# 20160901_MMPLATES.net
KiCad netlist of a schematic drawn in EAGLE
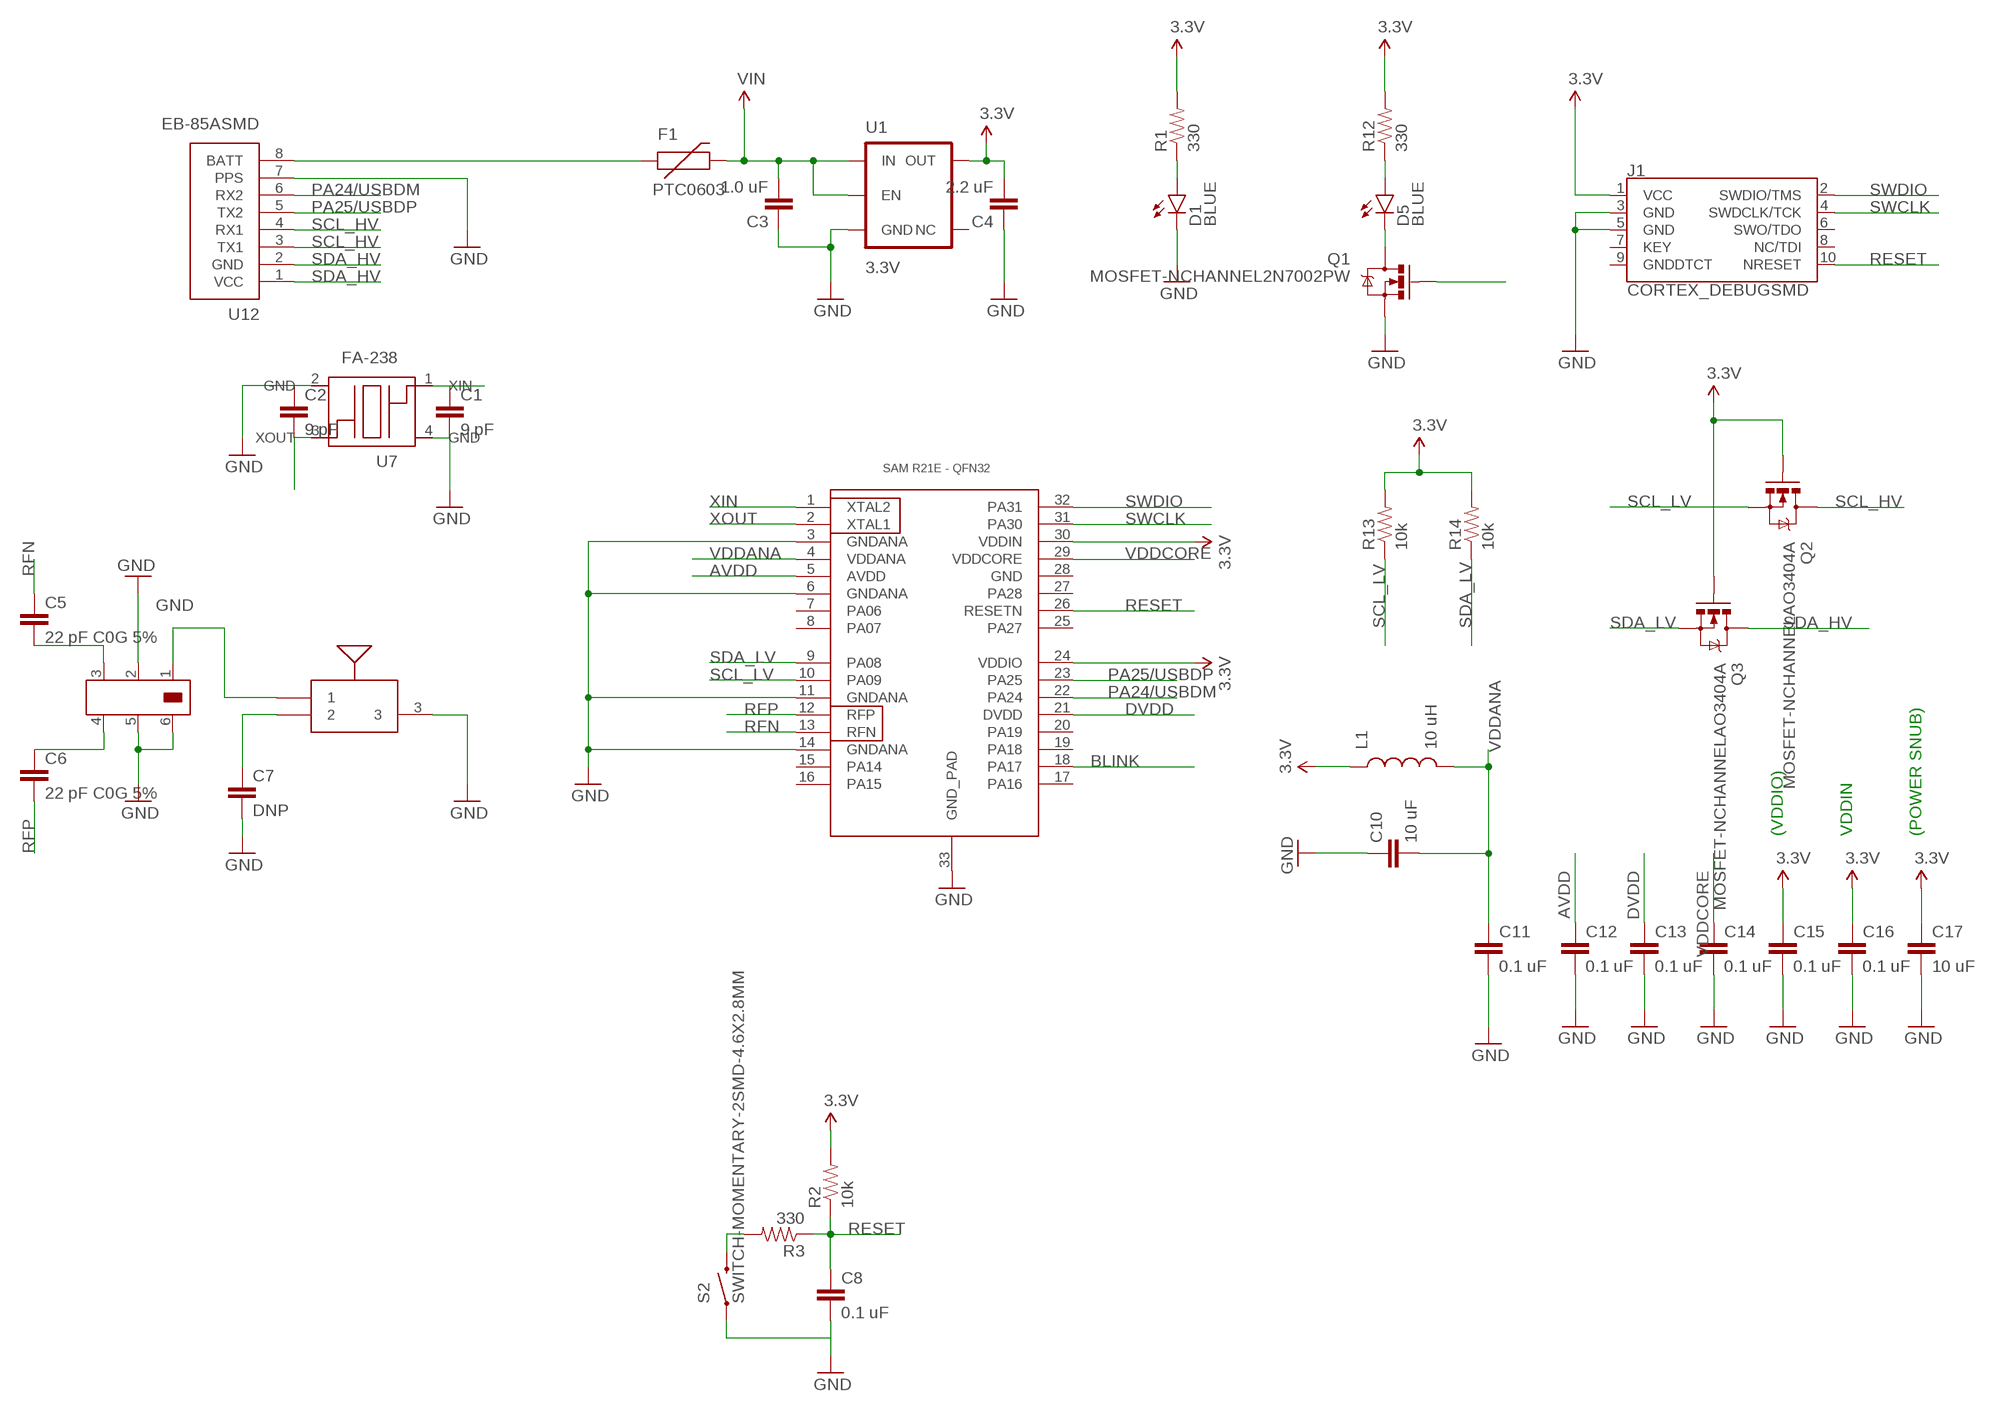
[diagram p0: schematic, sheet 1, part 1 of 2]
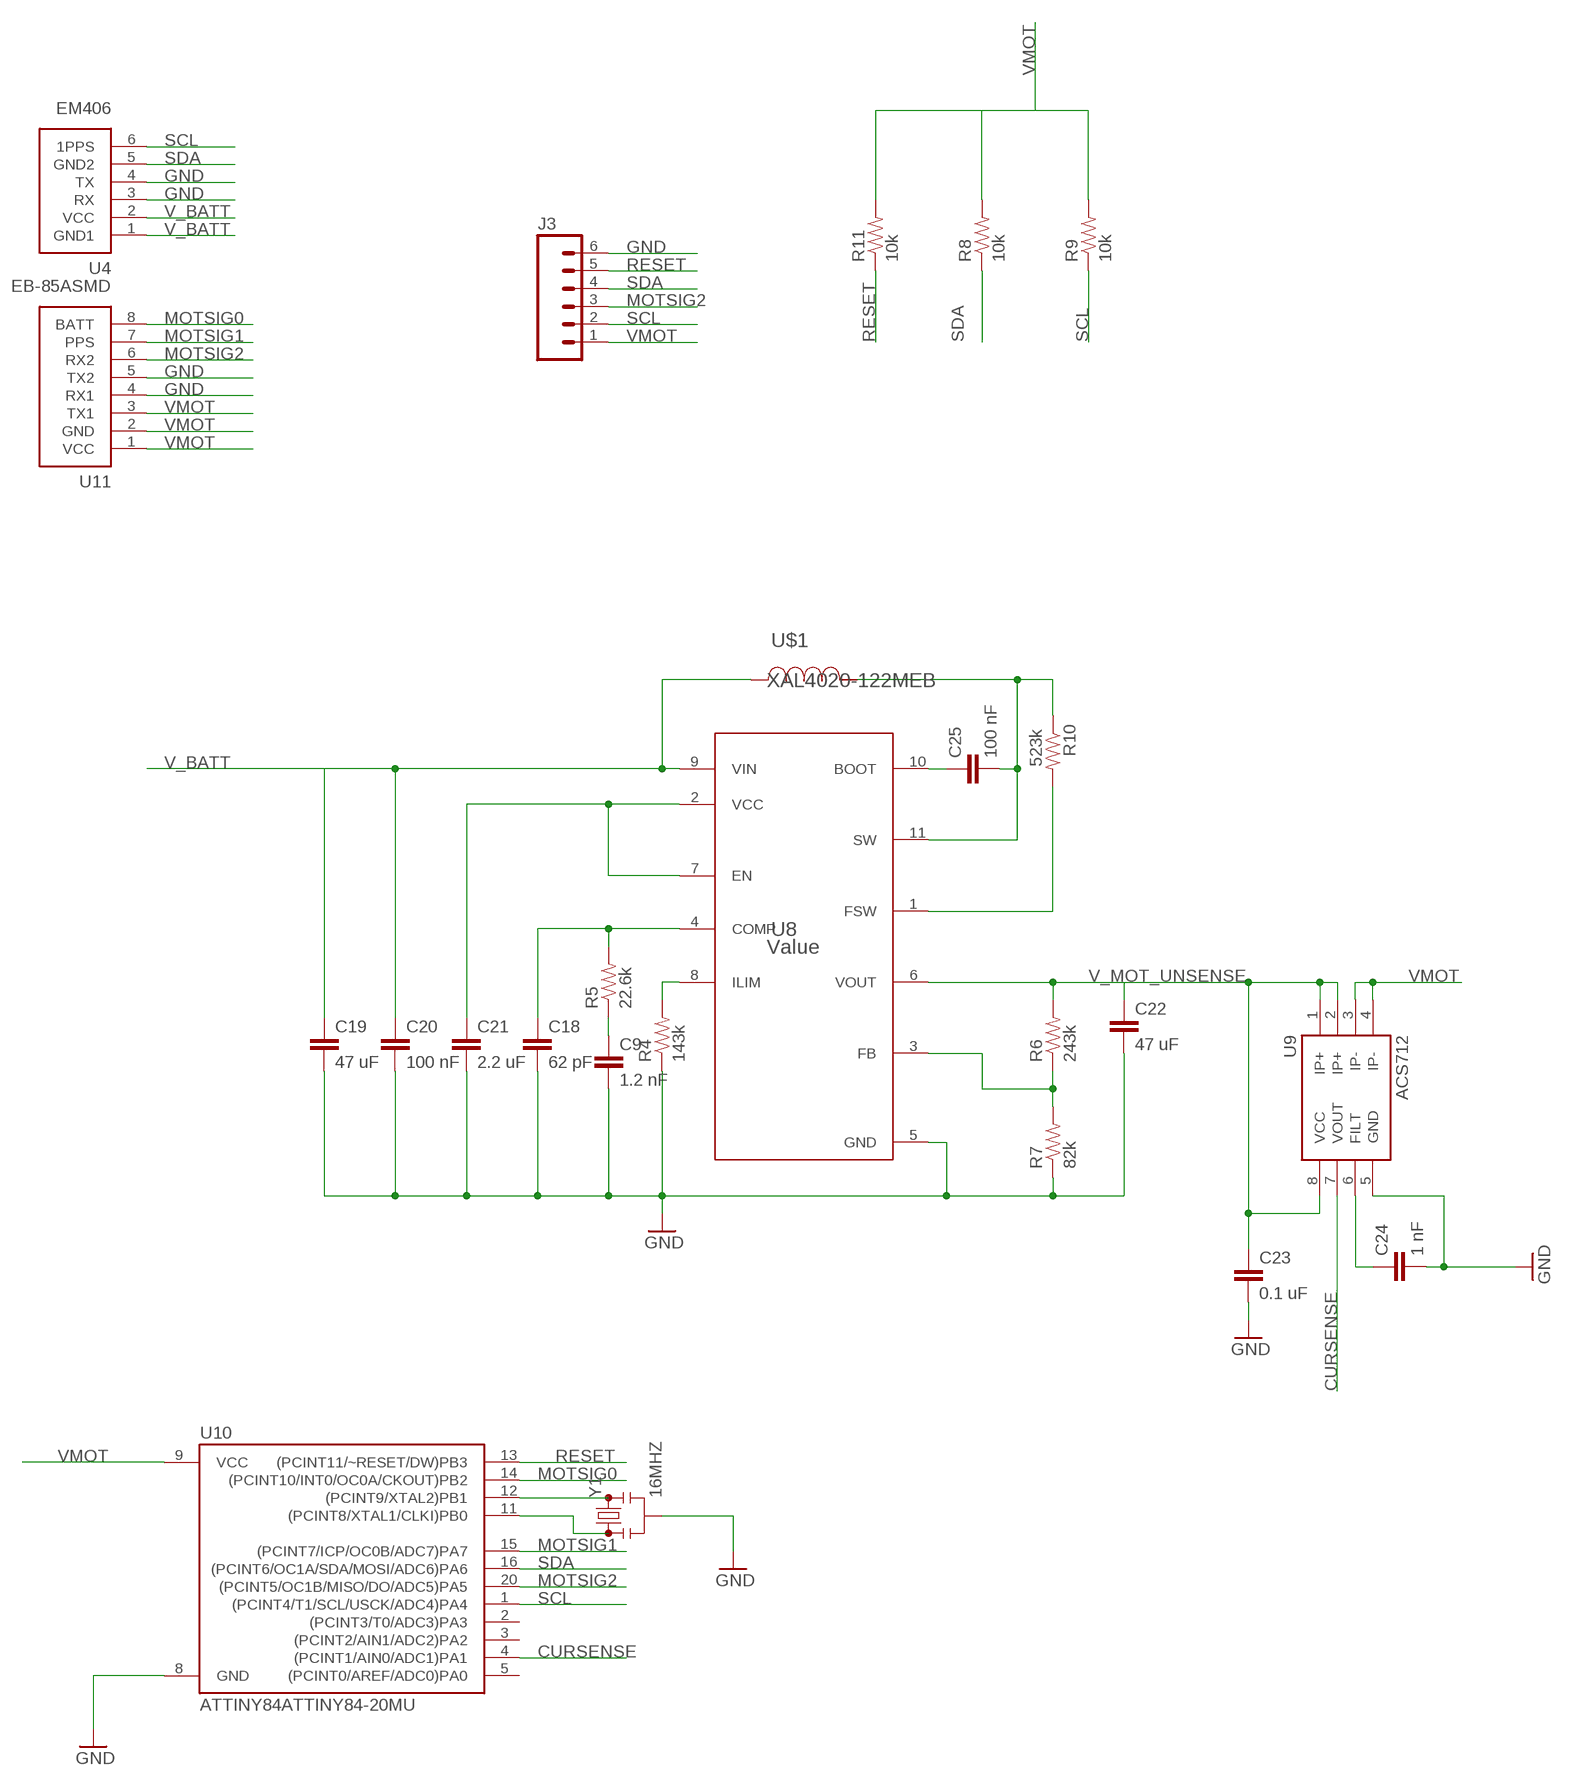
[diagram p1: schematic, sheet 1, part 2 of 2]

(export (version "E")
  (design (tool "Eeschema 10.0.6"))
  (components
    (comp (ref "C1")
      (value "9 pF")
      (footprint "eagle-import:0402-CAP")
      (libsource (lib "eagle-import") (part "CAP0402-CAP"))
    )
    (comp (ref "C2")
      (value "9 pF")
      (footprint "eagle-import:0402-CAP")
      (libsource (lib "eagle-import") (part "CAP0402-CAP"))
    )
    (comp (ref "C3")
      (value "1.0 uF")
      (footprint "eagle-import:0402-CAP")
      (libsource (lib "eagle-import") (part "CAP0402-CAP"))
    )
    (comp (ref "C4")
      (value "2.2 uF")
      (footprint "eagle-import:0402-CAP")
      (libsource (lib "eagle-import") (part "CAP0402-CAP"))
    )
    (comp (ref "C5")
      (value "22 pF C0G 5%")
      (footprint "eagle-import:0402-CAP")
      (libsource (lib "eagle-import") (part "CAP0402-CAP"))
    )
    (comp (ref "C6")
      (value "22 pF C0G 5%")
      (footprint "eagle-import:0402-CAP")
      (libsource (lib "eagle-import") (part "CAP0402-CAP"))
    )
    (comp (ref "C7")
      (value "DNP")
      (footprint "eagle-import:0402-CAP")
      (libsource (lib "eagle-import") (part "CAP0402-CAP"))
    )
    (comp (ref "C8")
      (value "0.1 uF")
      (footprint "eagle-import:0402-CAP")
      (libsource (lib "eagle-import") (part "CAP0402-CAP"))
    )
    (comp (ref "C9")
      (value "1.2 nF")
      (footprint "eagle-import:0805")
      (libsource (lib "eagle-import") (part "CAP0805"))
    )
    (comp (ref "C10")
      (value "10 uF")
      (footprint "eagle-import:0402-CAP")
      (libsource (lib "eagle-import") (part "CAP0402-CAP"))
    )
    (comp (ref "C11")
      (value "0.1 uF")
      (footprint "eagle-import:0402-CAP")
      (libsource (lib "eagle-import") (part "CAP0402-CAP"))
    )
    (comp (ref "C12")
      (value "0.1 uF")
      (footprint "eagle-import:0402-CAP")
      (libsource (lib "eagle-import") (part "CAP0402-CAP"))
    )
    (comp (ref "C13")
      (value "0.1 uF")
      (footprint "eagle-import:0402-CAP")
      (libsource (lib "eagle-import") (part "CAP0402-CAP"))
    )
    (comp (ref "C14")
      (value "0.1 uF")
      (footprint "eagle-import:0402-CAP")
      (libsource (lib "eagle-import") (part "CAP0402-CAP"))
    )
    (comp (ref "C15")
      (value "0.1 uF")
      (footprint "eagle-import:0402-CAP")
      (libsource (lib "eagle-import") (part "CAP0402-CAP"))
    )
    (comp (ref "C16")
      (value "0.1 uF")
      (footprint "eagle-import:0402-CAP")
      (libsource (lib "eagle-import") (part "CAP0402-CAP"))
    )
    (comp (ref "C17")
      (value "10 uF")
      (footprint "eagle-import:0402-CAP")
      (libsource (lib "eagle-import") (part "CAP0402-CAP"))
    )
    (comp (ref "C18")
      (value "62 pF")
      (footprint "eagle-import:0805")
      (libsource (lib "eagle-import") (part "CAP0805"))
    )
    (comp (ref "C19")
      (value "47 uF")
      (footprint "eagle-import:1206")
      (libsource (lib "eagle-import") (part "CAP1206"))
    )
    (comp (ref "C20")
      (value "100 nF")
      (footprint "eagle-import:0402-CAP")
      (libsource (lib "eagle-import") (part "CAP0402-CAP"))
    )
    (comp (ref "C21")
      (value "2.2 uF")
      (footprint "eagle-import:0603-CAP")
      (libsource (lib "eagle-import") (part "CAP0603-CAP"))
    )
    (comp (ref "C22")
      (value "47 uF")
      (footprint "eagle-import:1206")
      (libsource (lib "eagle-import") (part "CAP1206"))
    )
    (comp (ref "C23")
      (value "0.1 uF")
      (footprint "eagle-import:0402-CAP")
      (libsource (lib "eagle-import") (part "CAP0402-CAP"))
    )
    (comp (ref "C24")
      (value "1 nF")
      (footprint "eagle-import:0402-CAP")
      (libsource (lib "eagle-import") (part "CAP0402-CAP"))
    )
    (comp (ref "C25")
      (value "100 nF")
      (footprint "eagle-import:0402-CAP")
      (libsource (lib "eagle-import") (part "CAP0402-CAP"))
    )
    (comp (ref "D1")
      (value "BLUE")
      (footprint "eagle-import:LED-0603")
      (libsource (lib "eagle-import") (part "LED-BLUE0603"))
    )
    (comp (ref "D5")
      (value "BLUE")
      (footprint "eagle-import:LED-0603")
      (libsource (lib "eagle-import") (part "LED-BLUE0603"))
    )
    (comp (ref "F1")
      (value "PTC0603")
      (footprint "eagle-import:0603")
      (libsource (lib "eagle-import") (part "PTC0603"))
    )
    (comp (ref "J1")
      (value "CORTEX_DEBUGSMD")
      (footprint "eagle-import:SAMTECH_FTSH-105-01")
      (libsource (lib "eagle-import") (part "CORTEX_DEBUGSMD"))
    )
    (comp (ref "J3")
      (value "M06SMD-1MM")
      (footprint "eagle-import:1X06-1MM")
      (libsource (lib "eagle-import") (part "M06SMD-1MM"))
    )
    (comp (ref "L1")
      (value "10 uH")
      (footprint "eagle-import:0603")
      (libsource (lib "eagle-import") (part "INDUCTOR0603"))
    )
    (comp (ref "Q1")
      (value "MOSFET-NCHANNEL2N7002PW")
      (footprint "eagle-import:SOT323")
      (libsource (lib "eagle-import") (part "MOSFET-NCHANNEL2N7002PW"))
    )
    (comp (ref "Q2")
      (value "MOSFET-NCHANNELAO3404A")
      (footprint "eagle-import:SOT23-3")
      (libsource (lib "eagle-import") (part "MOSFET-NCHANNELAO3404A"))
    )
    (comp (ref "Q3")
      (value "MOSFET-NCHANNELAO3404A")
      (footprint "eagle-import:SOT23-3")
      (libsource (lib "eagle-import") (part "MOSFET-NCHANNELAO3404A"))
    )
    (comp (ref "R1")
      (value "330")
      (footprint "eagle-import:0402-RES")
      (libsource (lib "eagle-import") (part "RESISTOR0402-RES"))
    )
    (comp (ref "R2")
      (value "10k")
      (footprint "eagle-import:0402-RES")
      (libsource (lib "eagle-import") (part "RESISTOR0402-RES"))
    )
    (comp (ref "R3")
      (value "330")
      (footprint "eagle-import:0402-RES")
      (libsource (lib "eagle-import") (part "RESISTOR0402-RES"))
    )
    (comp (ref "R4")
      (value "143k")
      (footprint "eagle-import:1206")
      (libsource (lib "eagle-import") (part "SparkFun-Resistors_RESISTOR1206"))
    )
    (comp (ref "R5")
      (value "22.6k")
      (footprint "eagle-import:0402-RES")
      (libsource (lib "eagle-import") (part "RESISTOR0402-RES"))
    )
    (comp (ref "R6")
      (value "243k")
      (footprint "eagle-import:0402-RES")
      (libsource (lib "eagle-import") (part "RESISTOR0402-RES"))
    )
    (comp (ref "R7")
      (value "82k")
      (footprint "eagle-import:0603-RES")
      (libsource (lib "eagle-import") (part "RESISTOR0603-RES"))
    )
    (comp (ref "R8")
      (value "10k")
      (footprint "eagle-import:0402-RES")
      (libsource (lib "eagle-import") (part "RESISTOR0402-RES"))
    )
    (comp (ref "R9")
      (value "10k")
      (footprint "eagle-import:0402-RES")
      (libsource (lib "eagle-import") (part "RESISTOR0402-RES"))
    )
    (comp (ref "R10")
      (value "523k")
      (footprint "eagle-import:1206")
      (libsource (lib "eagle-import") (part "SparkFun-Resistors_RESISTOR1206"))
    )
    (comp (ref "R11")
      (value "10k")
      (footprint "eagle-import:0402-RES")
      (libsource (lib "eagle-import") (part "RESISTOR0402-RES"))
    )
    (comp (ref "R12")
      (value "330")
      (footprint "eagle-import:0402-RES")
      (libsource (lib "eagle-import") (part "RESISTOR0402-RES"))
    )
    (comp (ref "R13")
      (value "10k")
      (footprint "eagle-import:0402-RES")
      (libsource (lib "eagle-import") (part "RESISTOR0402-RES"))
    )
    (comp (ref "R14")
      (value "10k")
      (footprint "eagle-import:0402-RES")
      (libsource (lib "eagle-import") (part "RESISTOR0402-RES"))
    )
    (comp (ref "S2")
      (value "SWITCH-MOMENTARY-2SMD-4.6X2.8MM")
      (footprint "eagle-import:TACTILE_SWITCH_SMD_4.6X2.8MM")
      (libsource (lib "eagle-import") (part "SWITCH-MOMENTARY-2SMD-4.6X2.8MM"))
    )
    (comp (ref "U$1")
      (value "XAL4020-122MEB")
      (footprint "eagle-import:XAL4020")
      (libsource (lib "eagle-import") (part "XAL4020-122MEB"))
    )
    (comp (ref "U1")
      (value "3.3V")
      (footprint "eagle-import:SOT23-5")
      (libsource (lib "eagle-import") (part "V_REG_AP2112K-3.3V"))
    )
    (comp (ref "U2")
      (value "ATSAMR21E18A-MUT")
      (footprint "eagle-import:QFN32")
      (libsource (lib "eagle-import") (part "ATSAMR21E18A-MUT"))
    )
    (comp (ref "U4")
      (value "EM406")
      (footprint "eagle-import:EM406")
      (libsource (lib "eagle-import") (part "EM406"))
    )
    (comp (ref "U5")
      (value "PULSE_ANT_2.4GHZ")
      (footprint "eagle-import:ANT_BAR")
      (libsource (lib "eagle-import") (part "PULSE_ANT_2.4GHZ"))
    )
    (comp (ref "U6")
      (value "JOHANSON_2450BM15A0015E")
      (footprint "eagle-import:0805_BALUN")
      (libsource (lib "eagle-import") (part "JOHANSON_2450BM15A0015E"))
    )
    (comp (ref "U7")
      (value "FA-238")
      (footprint "eagle-import:FA-238")
      (libsource (lib "eagle-import") (part "FA-238"))
    )
    (comp (ref "U8")
      (value "Value")
      (footprint "eagle-import:RNR0011A")
      (fields
        (field (name "MANUFACTURER") "Texas Instruments")
        (field (name "MANUFACTURER_PART_NUMBER") "TPS61089RNRR")
      )
      (libsource (lib "eagle-import") (part "TPS61089RNRR"))
    )
    (comp (ref "U9")
      (value "ACS712")
      (footprint "eagle-import:SO08")
      (libsource (lib "eagle-import") (part "ACS712"))
    )
    (comp (ref "U10")
      (value "ATTINY84ATTINY84-20MU")
      (footprint "eagle-import:QFN20")
      (libsource (lib "eagle-import") (part "ATTINY84ATTINY84-20MU"))
    )
    (comp (ref "U11")
      (value "EB-85ASMD")
      (footprint "eagle-import:EB-85A")
      (libsource (lib "eagle-import") (part "EB-85ASMD"))
    )
    (comp (ref "U12")
      (value "EB-85ASMD")
      (footprint "eagle-import:EB-85A")
      (libsource (lib "eagle-import") (part "EB-85ASMD"))
    )
    (comp (ref "Y1")
      (value "16MHZ")
      (footprint "eagle-import:RESONATOR-SMD")
      (libsource (lib "eagle-import") (part "RESONATOR16MHZ"))
    )
  )
  (nets
    (net (code "1") (name "/AVDD") (class "Default")
      (node (ref "C12") (pin "1") (pinfunction "1_1") (pintype "passive"))
      (node (ref "U2") (pin "5") (pinfunction "AVDD_5") (pintype "bidirectional"))
    )
    (net (code "2") (name "/BLINK") (class "Default")
      (node (ref "Q1") (pin "1") (pinfunction "G_1") (pintype "passive"))
      (node (ref "U2") (pin "18") (pinfunction "PA17_18") (pintype "bidirectional"))
    )
    (net (code "3") (name "/CURSENSE") (class "Default")
      (node (ref "U10") (pin "4") (pinfunction "(PCINT1/AIN0/ADC1)PA1_4") (pintype "bidirectional"))
      (node (ref "U9") (pin "7") (pinfunction "VOUT_7") (pintype "bidirectional"))
    )
    (net (code "4") (name "/DVDD") (class "Default")
      (node (ref "C13") (pin "1") (pinfunction "1_1") (pintype "passive"))
      (node (ref "U2") (pin "21") (pinfunction "DVDD_21") (pintype "bidirectional"))
    )
    (net (code "5") (name "/MOTSIG0") (class "Default")
      (node (ref "U10") (pin "14") (pinfunction "(PCINT10/INT0/OC0A/CKOUT)PB2_14") (pintype "bidirectional"))
      (node (ref "U11") (pin "8") (pinfunction "BATT_8") (pintype "power_in"))
    )
    (net (code "6") (name "/MOTSIG1") (class "Default")
      (node (ref "U10") (pin "15") (pinfunction "(PCINT7/ICP/OC0B/ADC7)PA7_15") (pintype "bidirectional"))
      (node (ref "U11") (pin "7") (pinfunction "PPS_7") (pintype "output"))
    )
    (net (code "7") (name "/MOTSIG2") (class "Default")
      (node (ref "J3") (pin "3") (pinfunction "3_3") (pintype "passive"))
      (node (ref "U10") (pin "20") (pinfunction "(PCINT5/OC1B/MISO/DO/ADC5)PA5_20") (pintype "bidirectional"))
      (node (ref "U11") (pin "6") (pinfunction "RX2_6") (pintype "input"))
    )
    (net (code "8") (name "/PA24{slash}USBDM") (class "Default")
      (node (ref "U12") (pin "6") (pinfunction "RX2_6") (pintype "input"))
      (node (ref "U2") (pin "22") (pinfunction "PA24_22") (pintype "bidirectional"))
    )
    (net (code "9") (name "/PA25{slash}USBDP") (class "Default")
      (node (ref "U12") (pin "5") (pinfunction "TX2_5") (pintype "output"))
      (node (ref "U2") (pin "23") (pinfunction "PA25_23") (pintype "bidirectional"))
    )
    (net (code "10") (name "/RESET") (class "Default")
      (node (ref "C8") (pin "1") (pinfunction "1_1") (pintype "passive"))
      (node (ref "J1") (pin "10") (pinfunction "NRESET_10") (pintype "bidirectional"))
      (node (ref "J3") (pin "5") (pinfunction "5_5") (pintype "passive"))
      (node (ref "R11") (pin "1") (pinfunction "1_1") (pintype "passive"))
      (node (ref "R2") (pin "1") (pinfunction "1_1") (pintype "passive"))
      (node (ref "R3") (pin "1") (pinfunction "1_1") (pintype "passive"))
      (node (ref "U10") (pin "13") (pinfunction "(PCINT11/~{RESET/DW})PB3_13") (pintype "bidirectional"))
      (node (ref "U2") (pin "26") (pinfunction "RESETN_26") (pintype "bidirectional"))
    )
    (net (code "11") (name "/RFN") (class "Default")
      (node (ref "C5") (pin "1") (pinfunction "1_1") (pintype "passive"))
      (node (ref "U2") (pin "13") (pinfunction "RFN_13") (pintype "bidirectional"))
    )
    (net (code "12") (name "/RFP") (class "Default")
      (node (ref "C6") (pin "2") (pinfunction "2_2") (pintype "passive"))
      (node (ref "U2") (pin "12") (pinfunction "RFP_12") (pintype "bidirectional"))
    )
    (net (code "13") (name "/SCL") (class "Default")
      (node (ref "J3") (pin "2") (pinfunction "2_2") (pintype "passive"))
      (node (ref "R9") (pin "1") (pinfunction "1_1") (pintype "passive"))
      (node (ref "U10") (pin "1") (pinfunction "(PCINT4/T1/SCL/USCK/ADC4)PA4_1") (pintype "bidirectional"))
      (node (ref "U4") (pin "6") (pinfunction "1PPS_6") (pintype "bidirectional"))
    )
    (net (code "14") (name "/SCL_HV") (class "Default")
      (node (ref "Q2") (pin "3") (pinfunction "D_3") (pintype "passive"))
      (node (ref "U12") (pin "3") (pinfunction "TX1_3") (pintype "output"))
      (node (ref "U12") (pin "4") (pinfunction "RX1_4") (pintype "input"))
    )
    (net (code "15") (name "/SCL_LV") (class "Default")
      (node (ref "Q2") (pin "2") (pinfunction "S_2") (pintype "passive"))
      (node (ref "R13") (pin "1") (pinfunction "1_1") (pintype "passive"))
      (node (ref "U2") (pin "10") (pinfunction "PA09_10") (pintype "bidirectional"))
    )
    (net (code "16") (name "/SDA") (class "Default")
      (node (ref "J3") (pin "4") (pinfunction "4_4") (pintype "passive"))
      (node (ref "R8") (pin "1") (pinfunction "1_1") (pintype "passive"))
      (node (ref "U10") (pin "16") (pinfunction "(PCINT6/OC1A/SDA/MOSI/ADC6)PA6_16") (pintype "bidirectional"))
      (node (ref "U4") (pin "5") (pinfunction "GND2_5") (pintype "bidirectional"))
    )
    (net (code "17") (name "/SDA_HV") (class "Default")
      (node (ref "Q3") (pin "3") (pinfunction "D_3") (pintype "passive"))
      (node (ref "U12") (pin "1") (pinfunction "VCC_1") (pintype "power_in"))
      (node (ref "U12") (pin "2") (pinfunction "GND_2") (pintype "power_in"))
    )
    (net (code "18") (name "/SDA_LV") (class "Default")
      (node (ref "Q3") (pin "2") (pinfunction "S_2") (pintype "passive"))
      (node (ref "R14") (pin "1") (pinfunction "1_1") (pintype "passive"))
      (node (ref "U2") (pin "9") (pinfunction "PA08_9") (pintype "bidirectional"))
    )
    (net (code "19") (name "/SWCLK") (class "Default")
      (node (ref "J1") (pin "4") (pinfunction "SWDCLK/TCK_4") (pintype "bidirectional"))
      (node (ref "U2") (pin "31") (pinfunction "PA30_31") (pintype "bidirectional"))
    )
    (net (code "20") (name "/SWDIO") (class "Default")
      (node (ref "J1") (pin "2") (pinfunction "SWDIO/TMS_2") (pintype "bidirectional"))
      (node (ref "U2") (pin "32") (pinfunction "PA31_32") (pintype "bidirectional"))
    )
    (net (code "21") (name "/VDDANA") (class "Default")
      (node (ref "C10") (pin "2") (pinfunction "2_2") (pintype "passive"))
      (node (ref "C11") (pin "1") (pinfunction "1_1") (pintype "passive"))
      (node (ref "L1") (pin "2") (pinfunction "2_2") (pintype "passive"))
      (node (ref "U2") (pin "4") (pinfunction "VDDANA_4") (pintype "bidirectional"))
    )
    (net (code "22") (name "/VDDCORE") (class "Default")
      (node (ref "C14") (pin "1") (pinfunction "1_1") (pintype "passive"))
      (node (ref "U2") (pin "29") (pinfunction "VDDCORE_29") (pintype "bidirectional"))
    )
    (net (code "23") (name "/VMOT") (class "Default")
      (node (ref "J3") (pin "1") (pinfunction "1_1") (pintype "passive"))
      (node (ref "R11") (pin "2") (pinfunction "2_2") (pintype "passive"))
      (node (ref "R8") (pin "2") (pinfunction "2_2") (pintype "passive"))
      (node (ref "R9") (pin "2") (pinfunction "2_2") (pintype "passive"))
      (node (ref "U10") (pin "9") (pinfunction "VCC_9") (pintype "bidirectional"))
      (node (ref "U11") (pin "1") (pinfunction "VCC_1") (pintype "power_in"))
      (node (ref "U11") (pin "2") (pinfunction "GND_2") (pintype "power_in"))
      (node (ref "U11") (pin "3") (pinfunction "TX1_3") (pintype "output"))
      (node (ref "U9") (pin "3") (pinfunction "IP-_3") (pintype "bidirectional"))
      (node (ref "U9") (pin "4") (pinfunction "IP-_4") (pintype "bidirectional"))
    )
    (net (code "24") (name "/V_BATT") (class "Default")
      (node (ref "C19") (pin "1") (pinfunction "1_1") (pintype "passive"))
      (node (ref "C20") (pin "1") (pinfunction "1_1") (pintype "passive"))
      (node (ref "U$1") (pin "1") (pinfunction "1_1") (pintype "passive"))
      (node (ref "U4") (pin "1") (pinfunction "GND1_1") (pintype "bidirectional"))
      (node (ref "U4") (pin "2") (pinfunction "VCC_2") (pintype "bidirectional"))
      (node (ref "U8") (pin "9") (pinfunction "VIN_9") (pintype "power_in"))
    )
    (net (code "25") (name "/V_MOT_UNSENSE") (class "Default")
      (node (ref "C22") (pin "1") (pinfunction "1_1") (pintype "passive"))
      (node (ref "C23") (pin "1") (pinfunction "1_1") (pintype "passive"))
      (node (ref "R6") (pin "2") (pinfunction "2_2") (pintype "passive"))
      (node (ref "U8") (pin "6") (pinfunction "VOUT_6") (pintype "power_in"))
      (node (ref "U9") (pin "1") (pinfunction "IP+_1") (pintype "bidirectional"))
      (node (ref "U9") (pin "2") (pinfunction "IP+_2") (pintype "bidirectional"))
      (node (ref "U9") (pin "8") (pinfunction "VCC_8") (pintype "bidirectional"))
    )
    (net (code "26") (name "/XIN") (class "Default")
      (node (ref "C1") (pin "1") (pinfunction "1_1") (pintype "passive"))
      (node (ref "U2") (pin "1") (pinfunction "XTAL2_1") (pintype "bidirectional"))
      (node (ref "U7") (pin "1") (pinfunction "XIN_1") (pintype "bidirectional"))
    )
    (net (code "27") (name "/XOUT") (class "Default")
      (node (ref "C2") (pin "2") (pinfunction "2_2") (pintype "passive"))
      (node (ref "U2") (pin "2") (pinfunction "XTAL1_2") (pintype "bidirectional"))
      (node (ref "U7") (pin "3") (pinfunction "XOUT_3") (pintype "bidirectional"))
    )
    (net (code "28") (name "3.3V") (class "Default")
      (node (ref "C15") (pin "1") (pinfunction "1_1") (pintype "passive"))
      (node (ref "C16") (pin "1") (pinfunction "1_1") (pintype "passive"))
      (node (ref "C17") (pin "1") (pinfunction "1_1") (pintype "passive"))
      (node (ref "C4") (pin "2") (pinfunction "2_2") (pintype "passive"))
      (node (ref "J1") (pin "1") (pinfunction "VCC_1") (pintype "bidirectional"))
      (node (ref "L1") (pin "1") (pinfunction "1_1") (pintype "passive"))
      (node (ref "Q2") (pin "1") (pinfunction "G_1") (pintype "passive"))
      (node (ref "Q3") (pin "1") (pinfunction "G_1") (pintype "passive"))
      (node (ref "R1") (pin "2") (pinfunction "2_2") (pintype "passive"))
      (node (ref "R12") (pin "2") (pinfunction "2_2") (pintype "passive"))
      (node (ref "R13") (pin "2") (pinfunction "2_2") (pintype "passive"))
      (node (ref "R14") (pin "2") (pinfunction "2_2") (pintype "passive"))
      (node (ref "R2") (pin "2") (pinfunction "2_2") (pintype "passive"))
      (node (ref "U1") (pin "5") (pinfunction "OUT_5") (pintype "passive"))
      (node (ref "U2") (pin "24") (pinfunction "VDDIO_24") (pintype "bidirectional"))
      (node (ref "U2") (pin "30") (pinfunction "VDDIN_30") (pintype "bidirectional"))
    )
    (net (code "29") (name "GND") (class "Default")
      (node (ref "C1") (pin "2") (pinfunction "2_2") (pintype "passive"))
      (node (ref "C10") (pin "1") (pinfunction "1_1") (pintype "passive"))
      (node (ref "C11") (pin "2") (pinfunction "2_2") (pintype "passive"))
      (node (ref "C12") (pin "2") (pinfunction "2_2") (pintype "passive"))
      (node (ref "C13") (pin "2") (pinfunction "2_2") (pintype "passive"))
      (node (ref "C14") (pin "2") (pinfunction "2_2") (pintype "passive"))
      (node (ref "C15") (pin "2") (pinfunction "2_2") (pintype "passive"))
      (node (ref "C16") (pin "2") (pinfunction "2_2") (pintype "passive"))
      (node (ref "C17") (pin "2") (pinfunction "2_2") (pintype "passive"))
      (node (ref "C18") (pin "2") (pinfunction "2_2") (pintype "passive"))
      (node (ref "C19") (pin "2") (pinfunction "2_2") (pintype "passive"))
      (node (ref "C2") (pin "1") (pinfunction "1_1") (pintype "passive"))
      (node (ref "C20") (pin "2") (pinfunction "2_2") (pintype "passive"))
      (node (ref "C21") (pin "2") (pinfunction "2_2") (pintype "passive"))
      (node (ref "C22") (pin "2") (pinfunction "2_2") (pintype "passive"))
      (node (ref "C23") (pin "2") (pinfunction "2_2") (pintype "passive"))
      (node (ref "C24") (pin "2") (pinfunction "2_2") (pintype "passive"))
      (node (ref "C3") (pin "1") (pinfunction "1_1") (pintype "passive"))
      (node (ref "C4") (pin "1") (pinfunction "1_1") (pintype "passive"))
      (node (ref "C7") (pin "2") (pinfunction "2_2") (pintype "passive"))
      (node (ref "C8") (pin "2") (pinfunction "2_2") (pintype "passive"))
      (node (ref "C9") (pin "2") (pinfunction "2_2") (pintype "passive"))
      (node (ref "D1") (pin "C") (pinfunction "C_C") (pintype "passive"))
      (node (ref "J1") (pin "3") (pinfunction "GND_3") (pintype "bidirectional"))
      (node (ref "J1") (pin "5") (pinfunction "GND_5") (pintype "bidirectional"))
      (node (ref "J3") (pin "6") (pinfunction "6_6") (pintype "passive"))
      (node (ref "Q1") (pin "2") (pinfunction "S_2") (pintype "passive"))
      (node (ref "R4") (pin "1") (pinfunction "1_1") (pintype "passive"))
      (node (ref "R7") (pin "1") (pinfunction "1_1") (pintype "passive"))
      (node (ref "S2") (pin "1") (pinfunction "1_1") (pintype "passive"))
      (node (ref "S2") (pin "2") (pinfunction "1_2") (pintype "passive"))
      (node (ref "U1") (pin "2") (pinfunction "GND_2") (pintype "input"))
      (node (ref "U10") (pin "8") (pinfunction "GND_8") (pintype "bidirectional"))
      (node (ref "U11") (pin "4") (pinfunction "RX1_4") (pintype "input"))
      (node (ref "U11") (pin "5") (pinfunction "TX2_5") (pintype "output"))
      (node (ref "U12") (pin "7") (pinfunction "PPS_7") (pintype "output"))
      (node (ref "U2") (pin "11") (pinfunction "GNDANA_11") (pintype "bidirectional"))
      (node (ref "U2") (pin "14") (pinfunction "GNDANA_14") (pintype "bidirectional"))
      (node (ref "U2") (pin "3") (pinfunction "GNDANA_3") (pintype "bidirectional"))
      (node (ref "U2") (pin "33") (pinfunction "GND_PAD_33") (pintype "bidirectional"))
      (node (ref "U2") (pin "6") (pinfunction "GNDANA_6") (pintype "bidirectional"))
      (node (ref "U4") (pin "3") (pinfunction "RX_3") (pintype "bidirectional"))
      (node (ref "U4") (pin "4") (pinfunction "TX_4") (pintype "bidirectional"))
      (node (ref "U5") (pin "3") (pinfunction "3_3") (pintype "bidirectional"))
      (node (ref "U6") (pin "2") (pinfunction "2_2") (pintype "bidirectional"))
      (node (ref "U6") (pin "5") (pinfunction "5_5") (pintype "bidirectional"))
      (node (ref "U6") (pin "6") (pinfunction "6_6") (pintype "bidirectional"))
      (node (ref "U7") (pin "2") (pinfunction "GND_2") (pintype "bidirectional"))
      (node (ref "U7") (pin "4") (pinfunction "GND_4") (pintype "bidirectional"))
      (node (ref "U8") (pin "5") (pinfunction "GND_5") (pintype "power_in"))
      (node (ref "U9") (pin "5") (pinfunction "GND_5") (pintype "bidirectional"))
      (node (ref "Y1") (pin "2") (pinfunction "2_2") (pintype "passive"))
    )
    (net (code "30") (name "Net-(C5-Pad2)") (class "Default")
      (node (ref "C5") (pin "2") (pinfunction "2_2") (pintype "passive"))
      (node (ref "U6") (pin "3") (pinfunction "3_3") (pintype "bidirectional"))
    )
    (net (code "31") (name "Net-(C6-Pad1)") (class "Default")
      (node (ref "C6") (pin "1") (pinfunction "1_1") (pintype "passive"))
      (node (ref "U6") (pin "4") (pinfunction "4_4") (pintype "bidirectional"))
    )
    (net (code "32") (name "Net-(C7-Pad1)") (class "Default")
      (node (ref "C7") (pin "1") (pinfunction "1_1") (pintype "passive"))
      (node (ref "U5") (pin "2") (pinfunction "2_2") (pintype "bidirectional"))
    )
    (net (code "33") (name "Net-(C9-Pad1)") (class "Default")
      (node (ref "C9") (pin "1") (pinfunction "1_1") (pintype "passive"))
      (node (ref "R5") (pin "1") (pinfunction "1_1") (pintype "passive"))
    )
    (net (code "34") (name "Net-(D1-PadA)") (class "Default")
      (node (ref "D1") (pin "A") (pinfunction "A_A") (pintype "passive"))
      (node (ref "R1") (pin "1") (pinfunction "1_1") (pintype "passive"))
    )
    (net (code "35") (name "Net-(D5-PadA)") (class "Default")
      (node (ref "D5") (pin "A") (pinfunction "A_A") (pintype "passive"))
      (node (ref "R12") (pin "1") (pinfunction "1_1") (pintype "passive"))
    )
    (net (code "36") (name "Net-(Q1-D)") (class "Default")
      (node (ref "D5") (pin "C") (pinfunction "C_C") (pintype "passive"))
      (node (ref "Q1") (pin "3") (pinfunction "D_3") (pintype "passive"))
    )
    (net (code "37") (name "Net-(R3-Pad2)") (class "Default")
      (node (ref "R3") (pin "2") (pinfunction "2_2") (pintype "passive"))
      (node (ref "S2") (pin "3") (pinfunction "2_3") (pintype "passive"))
      (node (ref "S2") (pin "4") (pinfunction "2_4") (pintype "passive"))
    )
    (net (code "38") (name "Net-(U5-Pad1)") (class "Default")
      (node (ref "U5") (pin "1") (pinfunction "1_1") (pintype "bidirectional"))
      (node (ref "U6") (pin "1") (pinfunction "1_1") (pintype "bidirectional"))
    )
    (net (code "39") (name "Net-(U8-BOOT)") (class "Default")
      (node (ref "C25") (pin "1") (pinfunction "1_1") (pintype "passive"))
      (node (ref "U8") (pin "10") (pinfunction "BOOT_10") (pintype "power_in"))
    )
    (net (code "40") (name "Net-(U8-COMP)") (class "Default")
      (node (ref "C18") (pin "1") (pinfunction "1_1") (pintype "passive"))
      (node (ref "R5") (pin "2") (pinfunction "2_2") (pintype "passive"))
      (node (ref "U8") (pin "4") (pinfunction "COMP_4") (pintype "output"))
    )
    (net (code "41") (name "Net-(U8-EN)") (class "Default")
      (node (ref "C21") (pin "1") (pinfunction "1_1") (pintype "passive"))
      (node (ref "U8") (pin "2") (pinfunction "VCC_2") (pintype "power_in"))
      (node (ref "U8") (pin "7") (pinfunction "EN_7") (pintype "input"))
    )
    (net (code "42") (name "Net-(U8-FB)") (class "Default")
      (node (ref "R6") (pin "1") (pinfunction "1_1") (pintype "passive"))
      (node (ref "R7") (pin "2") (pinfunction "2_2") (pintype "passive"))
      (node (ref "U8") (pin "3") (pinfunction "FB_3") (pintype "input"))
    )
    (net (code "43") (name "Net-(U8-FSW)") (class "Default")
      (node (ref "R10") (pin "2") (pinfunction "2_2") (pintype "passive"))
      (node (ref "U8") (pin "1") (pinfunction "FSW_1") (pintype "input"))
    )
    (net (code "44") (name "Net-(U8-ILIM)") (class "Default")
      (node (ref "R4") (pin "2") (pinfunction "2_2") (pintype "passive"))
      (node (ref "U8") (pin "8") (pinfunction "ILIM_8") (pintype "input"))
    )
    (net (code "45") (name "Net-(U8-SW)") (class "Default")
      (node (ref "C25") (pin "2") (pinfunction "2_2") (pintype "passive"))
      (node (ref "R10") (pin "1") (pinfunction "1_1") (pintype "passive"))
      (node (ref "U$1") (pin "2") (pinfunction "2_2") (pintype "passive"))
      (node (ref "U8") (pin "11") (pinfunction "SW_11") (pintype "power_in"))
    )
    (net (code "46") (name "Net-(U9-FILT)") (class "Default")
      (node (ref "C24") (pin "1") (pinfunction "1_1") (pintype "passive"))
      (node (ref "U9") (pin "6") (pinfunction "FILT_6") (pintype "bidirectional"))
    )
    (net (code "47") (name "Net-(U10-(PCINT8{slash}XTAL1{slash}CLKI)PB0)") (class "Default")
      (node (ref "U10") (pin "11") (pinfunction "(PCINT8/XTAL1/CLKI)PB0_11") (pintype "bidirectional"))
      (node (ref "Y1") (pin "1") (pinfunction "1_1") (pintype "passive"))
    )
    (net (code "48") (name "Net-(U10-(PCINT9{slash}XTAL2)PB1)") (class "Default")
      (node (ref "U10") (pin "12") (pinfunction "(PCINT9/XTAL2)PB1_12") (pintype "bidirectional"))
      (node (ref "Y1") (pin "3") (pinfunction "3_3") (pintype "passive"))
    )
    (net (code "49") (name "Net-(U12-BATT)") (class "Default")
      (node (ref "F1") (pin "1") (pinfunction "1_1") (pintype "bidirectional"))
      (node (ref "U12") (pin "8") (pinfunction "BATT_8") (pintype "power_in"))
    )
    (net (code "50") (name "VIN") (class "Default")
      (node (ref "C3") (pin "2") (pinfunction "2_2") (pintype "passive"))
      (node (ref "F1") (pin "2") (pinfunction "2_2") (pintype "bidirectional"))
      (node (ref "U1") (pin "1") (pinfunction "IN_1") (pintype "input"))
      (node (ref "U1") (pin "3") (pinfunction "EN_3") (pintype "input"))
    )
    (net (code "51") (name "unconnected-(J1-GNDDTCT-Pad9)") (class "Default")
      (node (ref "J1") (pin "9") (pinfunction "GNDDTCT_9") (pintype "bidirectional"))
    )
    (net (code "52") (name "unconnected-(J1-KEY-Pad7)") (class "Default")
      (node (ref "J1") (pin "7") (pinfunction "KEY_7") (pintype "bidirectional"))
    )
    (net (code "53") (name "unconnected-(J1-NC{slash}TDI-Pad8)") (class "Default")
      (node (ref "J1") (pin "8") (pinfunction "NC/TDI_8") (pintype "bidirectional"))
    )
    (net (code "54") (name "unconnected-(J1-SWO{slash}TDO-Pad6)") (class "Default")
      (node (ref "J1") (pin "6") (pinfunction "SWO/TDO_6") (pintype "bidirectional"))
    )
    (net (code "55") (name "unconnected-(U1-NC-Pad4)") (class "Default")
      (node (ref "U1") (pin "4") (pinfunction "NC_4") (pintype "input"))
    )
    (net (code "56") (name "unconnected-(U2-GND-Pad28)") (class "Default")
      (node (ref "U2") (pin "28") (pinfunction "GND_28") (pintype "bidirectional"))
    )
    (net (code "57") (name "unconnected-(U2-PA06-Pad7)") (class "Default")
      (node (ref "U2") (pin "7") (pinfunction "PA06_7") (pintype "bidirectional"))
    )
    (net (code "58") (name "unconnected-(U2-PA07-Pad8)") (class "Default")
      (node (ref "U2") (pin "8") (pinfunction "PA07_8") (pintype "bidirectional"))
    )
    (net (code "59") (name "unconnected-(U2-PA14-Pad15)") (class "Default")
      (node (ref "U2") (pin "15") (pinfunction "PA14_15") (pintype "bidirectional"))
    )
    (net (code "60") (name "unconnected-(U2-PA15-Pad16)") (class "Default")
      (node (ref "U2") (pin "16") (pinfunction "PA15_16") (pintype "bidirectional"))
    )
    (net (code "61") (name "unconnected-(U2-PA16-Pad17)") (class "Default")
      (node (ref "U2") (pin "17") (pinfunction "PA16_17") (pintype "bidirectional"))
    )
    (net (code "62") (name "unconnected-(U2-PA18-Pad19)") (class "Default")
      (node (ref "U2") (pin "19") (pinfunction "PA18_19") (pintype "bidirectional"))
    )
    (net (code "63") (name "unconnected-(U2-PA19-Pad20)") (class "Default")
      (node (ref "U2") (pin "20") (pinfunction "PA19_20") (pintype "bidirectional"))
    )
    (net (code "64") (name "unconnected-(U2-PA27-Pad25)") (class "Default")
      (node (ref "U2") (pin "25") (pinfunction "PA27_25") (pintype "bidirectional"))
    )
    (net (code "65") (name "unconnected-(U2-PA28-Pad27)") (class "Default")
      (node (ref "U2") (pin "27") (pinfunction "PA28_27") (pintype "bidirectional"))
    )
    (net (code "66") (name "unconnected-(U10-(PCINT0{slash}AREF{slash}ADC0)PA0-Pad5)") (class "Default")
      (node (ref "U10") (pin "5") (pinfunction "(PCINT0/AREF/ADC0)PA0_5") (pintype "bidirectional"))
    )
    (net (code "67") (name "unconnected-(U10-(PCINT2{slash}AIN1{slash}ADC2)PA2-Pad3)") (class "Default")
      (node (ref "U10") (pin "3") (pinfunction "(PCINT2/AIN1/ADC2)PA2_3") (pintype "bidirectional"))
    )
    (net (code "68") (name "unconnected-(U10-(PCINT3{slash}T0{slash}ADC3)PA3-Pad2)") (class "Default")
      (node (ref "U10") (pin "2") (pinfunction "(PCINT3/T0/ADC3)PA3_2") (pintype "bidirectional"))
    )
  )
)
